# M_B_block_base.net
KiCad netlist of a schematic drawn in EAGLE
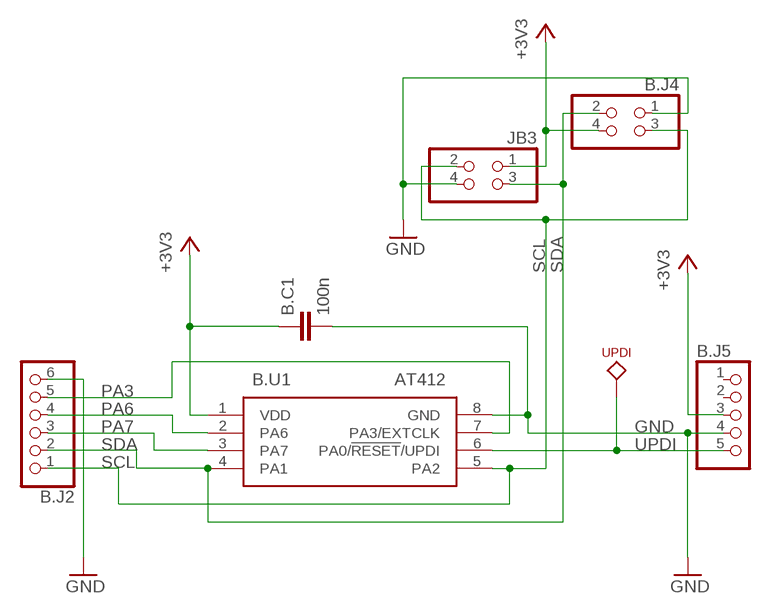
[diagram p0: schematic, sheet 1]

(export (version "E")
  (design (tool "Eeschema 10.0.6"))
  (components
    (comp (ref "B.C1")
      (value "100n")
      (footprint "eagle-import:C0603")
      (libsource (lib "eagle-import") (part "C-EUC0603"))
    )
    (comp (ref "B.J2")
      (value "PINHD-1X6")
      (footprint "eagle-import:1X06")
      (libsource (lib "eagle-import") (part "PINHD-1X6"))
    )
    (comp (ref "B.J4")
      (value "PINHD-2X2")
      (footprint "eagle-import:2X02")
      (libsource (lib "eagle-import") (part "PINHD-2X2"))
    )
    (comp (ref "B.J5")
      (value "PINHD-1X5")
      (footprint "eagle-import:1X05")
      (libsource (lib "eagle-import") (part "PINHD-1X5"))
    )
    (comp (ref "B.U1")
      (value "AT412")
      (footprint "eagle-import:SOIC127P600X175-8N")
      (fields
        (field (name "MANUFACTURER_PART_NUMBER") "ATTINY412-SSN")
        (field (name "MOUSER_PART_NUMBER") "579-ATTINY412-SSN")
      )
      (libsource (lib "eagle-import") (part "ATTINY412-SSN"))
    )
    (comp (ref "JB3")
      (value "PINHD-2X2")
      (footprint "eagle-import:2X02")
      (libsource (lib "eagle-import") (part "PINHD-2X2"))
    )
    (comp (ref "UPDI")
      (value "TPTP")
      (footprint "eagle-import:TP")
      (libsource (lib "eagle-import") (part "TPTP"))
    )
  )
  (nets
    (net (code "1") (name "+3V3") (class "Default")
      (node (ref "B.C1") (pin "1") (pinfunction "1_1") (pintype "passive"))
      (node (ref "B.J4") (pin "4") (pinfunction "4_4") (pintype "passive"))
      (node (ref "B.J5") (pin "3") (pinfunction "3_3") (pintype "passive"))
      (node (ref "B.U1") (pin "1") (pinfunction "VDD_1") (pintype "bidirectional"))
      (node (ref "JB3") (pin "1") (pinfunction "1_1") (pintype "passive"))
    )
    (net (code "2") (name "/PA3") (class "Default")
      (node (ref "B.J2") (pin "5") (pinfunction "5_5") (pintype "passive"))
      (node (ref "B.U1") (pin "7") (pinfunction "PA3/EXTCLK_7") (pintype "bidirectional"))
    )
    (net (code "3") (name "/PA6") (class "Default")
      (node (ref "B.J2") (pin "4") (pinfunction "4_4") (pintype "passive"))
      (node (ref "B.U1") (pin "2") (pinfunction "PA6_2") (pintype "bidirectional"))
    )
    (net (code "4") (name "/PA7") (class "Default")
      (node (ref "B.J2") (pin "3") (pinfunction "3_3") (pintype "passive"))
      (node (ref "B.U1") (pin "3") (pinfunction "PA7_3") (pintype "bidirectional"))
    )
    (net (code "5") (name "/SCL") (class "Default")
      (node (ref "B.J2") (pin "1") (pinfunction "1_1") (pintype "passive"))
      (node (ref "B.J4") (pin "3") (pinfunction "3_3") (pintype "passive"))
      (node (ref "B.U1") (pin "5") (pinfunction "PA2_5") (pintype "bidirectional"))
      (node (ref "JB3") (pin "2") (pinfunction "2_2") (pintype "passive"))
    )
    (net (code "6") (name "/SDA") (class "Default")
      (node (ref "B.J2") (pin "2") (pinfunction "2_2") (pintype "passive"))
      (node (ref "B.J4") (pin "2") (pinfunction "2_2") (pintype "passive"))
      (node (ref "B.U1") (pin "4") (pinfunction "PA1_4") (pintype "bidirectional"))
      (node (ref "JB3") (pin "3") (pinfunction "3_3") (pintype "passive"))
    )
    (net (code "7") (name "/UPDI") (class "Default")
      (node (ref "B.J5") (pin "5") (pinfunction "5_5") (pintype "passive"))
      (node (ref "B.U1") (pin "6") (pinfunction "PA0/~{RESET}/UPDI_6") (pintype "bidirectional"))
      (node (ref "UPDI") (pin "P$1") (pinfunction "P$1_P$1") (pintype "bidirectional"))
    )
    (net (code "8") (name "GND") (class "Default")
      (node (ref "B.C1") (pin "2") (pinfunction "2_2") (pintype "passive"))
      (node (ref "B.J2") (pin "6") (pinfunction "6_6") (pintype "passive"))
      (node (ref "B.J4") (pin "1") (pinfunction "1_1") (pintype "passive"))
      (node (ref "B.J5") (pin "4") (pinfunction "4_4") (pintype "passive"))
      (node (ref "B.U1") (pin "8") (pinfunction "GND_8") (pintype "bidirectional"))
      (node (ref "JB3") (pin "4") (pinfunction "4_4") (pintype "passive"))
    )
    (net (code "9") (name "unconnected-(B.J5-Pad1)") (class "Default")
      (node (ref "B.J5") (pin "1") (pinfunction "1_1") (pintype "passive"))
    )
    (net (code "10") (name "unconnected-(B.J5-Pad2)") (class "Default")
      (node (ref "B.J5") (pin "2") (pinfunction "2_2") (pintype "passive"))
    )
  )
)
